# untitled11111.net
KiCad netlist of a schematic drawn in EAGLE
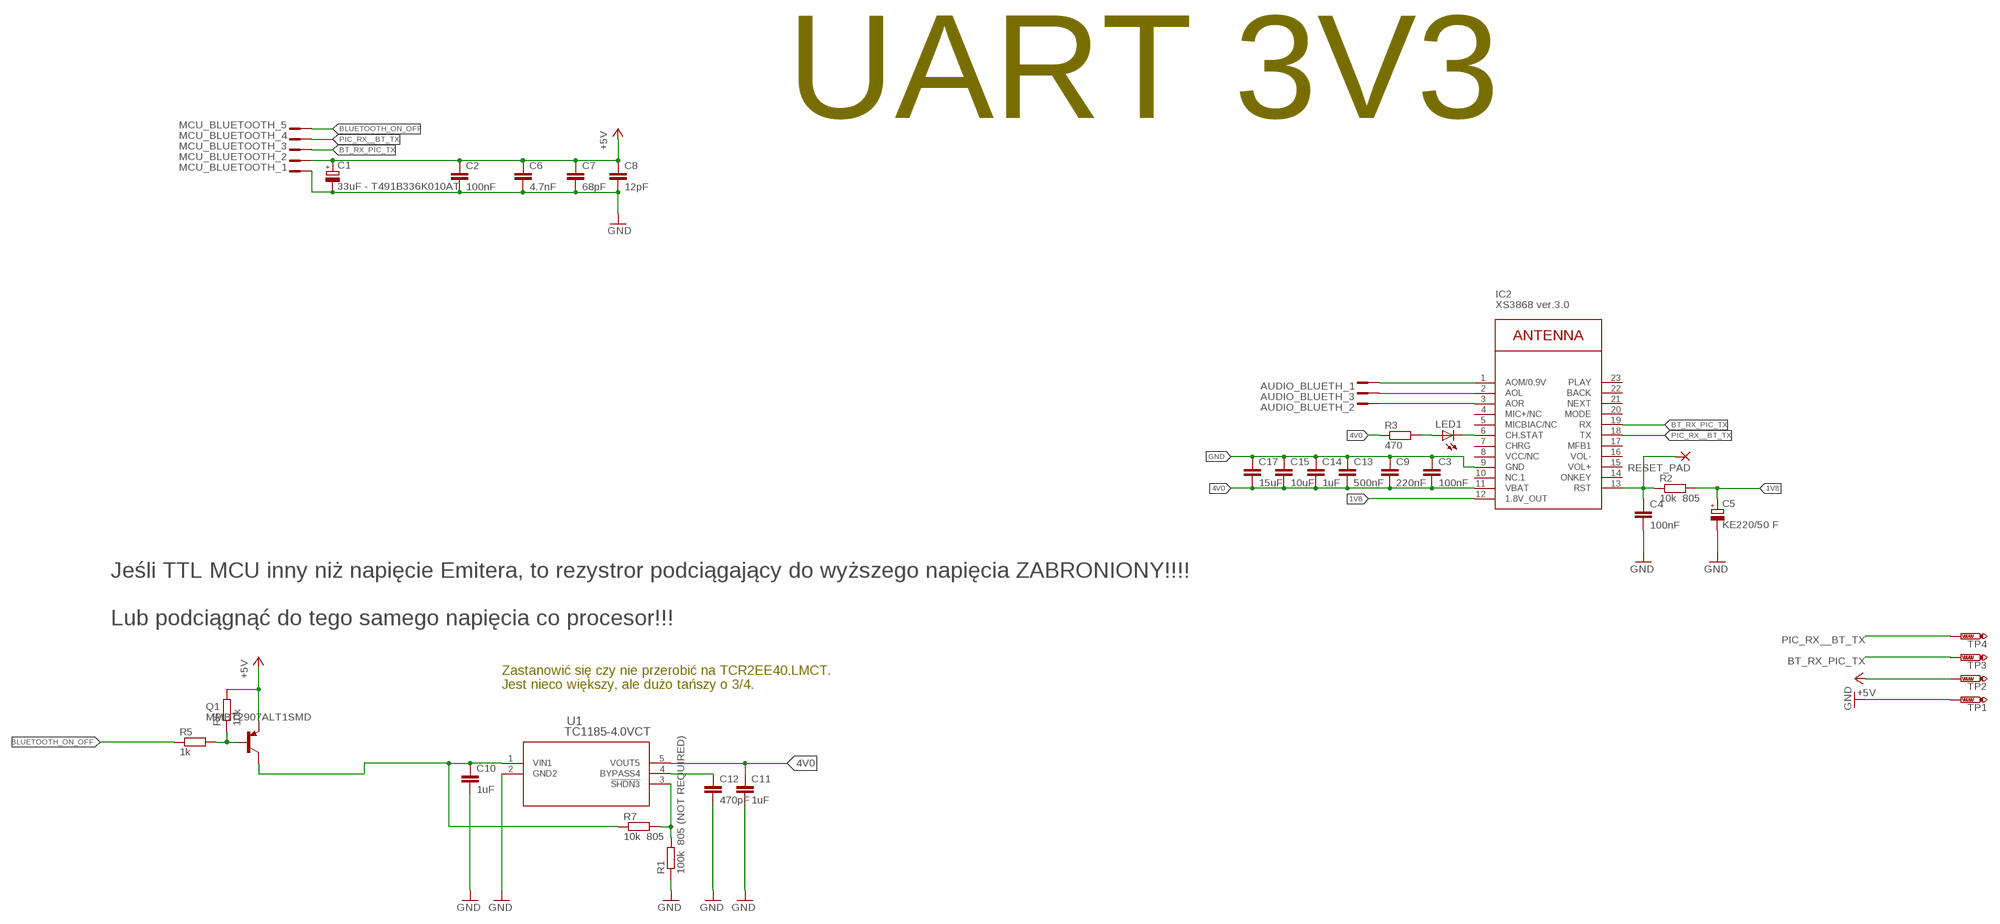
[diagram p0: schematic, sheet 1]

(export (version "E")
  (design (tool "Eeschema 10.0.6"))
  (components
    (comp (ref "AUDIO_BLUETH")
      (value "JST_3_PIN_B3B-PH-KS")
      (footprint "eagle-import:B3B-PH-KS")
      (libsource (lib "eagle-import") (part "JST_3_PIN_B3B-PH-KS"))
    )
    (comp (ref "C1")
      (value "33uF - T491B336K010AT")
      (footprint "eagle-import:SMC_C")
      (libsource (lib "eagle-import") (part "resistor_CPOL-EUSMCC"))
    )
    (comp (ref "C2")
      (value "100nF")
      (footprint "eagle-import:C0805")
      (libsource (lib "eagle-import") (part "C-EUC0805"))
    )
    (comp (ref "C3")
      (value "100nF")
      (footprint "eagle-import:C0805")
      (libsource (lib "eagle-import") (part "C-EUC0805"))
    )
    (comp (ref "C4")
      (value "100nF")
      (footprint "eagle-import:C0805")
      (libsource (lib "eagle-import") (part "C-EUC0805"))
    )
    (comp (ref "C5")
      (value "KE220/50 F")
      (footprint "eagle-import:PANASONIC_G")
      (libsource (lib "eagle-import") (part "CPOL-EUG"))
    )
    (comp (ref "C6")
      (value "4.7nF")
      (footprint "eagle-import:C0805")
      (libsource (lib "eagle-import") (part "C-EUC0805"))
    )
    (comp (ref "C7")
      (value "68pF")
      (footprint "eagle-import:C0805")
      (libsource (lib "eagle-import") (part "C-EUC0805"))
    )
    (comp (ref "C8")
      (value "12pF")
      (footprint "eagle-import:C0805")
      (libsource (lib "eagle-import") (part "C-EUC0805"))
    )
    (comp (ref "C9")
      (value "220nF")
      (footprint "eagle-import:C0805")
      (libsource (lib "eagle-import") (part "C-EUC0805"))
    )
    (comp (ref "C10")
      (value "1uF")
      (footprint "eagle-import:C0805")
      (libsource (lib "eagle-import") (part "C-EUC0805"))
    )
    (comp (ref "C11")
      (value "1uF")
      (footprint "eagle-import:C0805")
      (libsource (lib "eagle-import") (part "C-EUC0805"))
    )
    (comp (ref "C12")
      (value "470pF")
      (footprint "eagle-import:C0805")
      (libsource (lib "eagle-import") (part "C-EUC0805"))
    )
    (comp (ref "C13")
      (value "500nF")
      (footprint "eagle-import:C0805")
      (libsource (lib "eagle-import") (part "C-EUC0805"))
    )
    (comp (ref "C14")
      (value "1uF")
      (footprint "eagle-import:C0805")
      (libsource (lib "eagle-import") (part "C-EUC0805"))
    )
    (comp (ref "C15")
      (value "10uF")
      (footprint "eagle-import:C0805")
      (libsource (lib "eagle-import") (part "C-EUC0805"))
    )
    (comp (ref "C17")
      (value "15uF")
      (footprint "eagle-import:C0805")
      (libsource (lib "eagle-import") (part "C-EUC0805"))
    )
    (comp (ref "IC2")
      (value "XS3868 ver.3.0")
      (footprint "eagle-import:WIRELESS-BLUETOOTH-XS3868")
      (libsource (lib "eagle-import") (part "WIRELESS-BLUETOOTH-XS3868"))
    )
    (comp (ref "LED1")
      (value "LEDSML0805")
      (footprint "eagle-import:SML0805")
      (libsource (lib "eagle-import") (part "LEDSML0805"))
    )
    (comp (ref "MCU_BLUETOOTH")
      (value "JST_5_PIN_B5B-PH-KS")
      (footprint "eagle-import:B5B-PH-KS")
      (libsource (lib "eagle-import") (part "JST_5_PIN_B5B-PH-KS"))
    )
    (comp (ref "Q1")
      (value "MMBT2907ALT1SMD")
      (footprint "eagle-import:SOT23-BEC")
      (libsource (lib "eagle-import") (part "MMBT2907SMDALT1"))
    )
    (comp (ref "R1")
      (value "100k 805 (NOT REQUIRED)")
      (footprint "eagle-import:M0805")
      (libsource (lib "eagle-import") (part "R-EU_M0805"))
    )
    (comp (ref "R2")
      (value "10k 805")
      (footprint "eagle-import:M0805")
      (libsource (lib "eagle-import") (part "R-EU_M0805"))
    )
    (comp (ref "R3")
      (value "470")
      (footprint "eagle-import:M0805")
      (libsource (lib "eagle-import") (part "R-EU_M0805"))
    )
    (comp (ref "R5")
      (value "1k")
      (footprint "eagle-import:M0805")
      (libsource (lib "eagle-import") (part "R-EU_M0805"))
    )
    (comp (ref "R6")
      (value "10k")
      (footprint "eagle-import:M0805")
      (libsource (lib "eagle-import") (part "R-EU_M0805"))
    )
    (comp (ref "R7")
      (value "10k 805")
      (footprint "eagle-import:M0805")
      (libsource (lib "eagle-import") (part "R-EU_M0805"))
    )
    (comp (ref "RESET_PAD")
      (value "SMD2")
      (footprint "eagle-import:SMD1,27-2,54")
      (libsource (lib "eagle-import") (part "SMD2"))
    )
    (comp (ref "TP1")
      (value "PTR1B1,27")
      (footprint "eagle-import:B1,27")
      (libsource (lib "eagle-import") (part "PTR1B1,27"))
    )
    (comp (ref "TP2")
      (value "PTR1B1,27")
      (footprint "eagle-import:B1,27")
      (libsource (lib "eagle-import") (part "PTR1B1,27"))
    )
    (comp (ref "TP3")
      (value "PTR1B1,27")
      (footprint "eagle-import:B1,27")
      (libsource (lib "eagle-import") (part "PTR1B1,27"))
    )
    (comp (ref "TP4")
      (value "PTR1B1,27")
      (footprint "eagle-import:B1,27")
      (libsource (lib "eagle-import") (part "PTR1B1,27"))
    )
    (comp (ref "U1")
      (value "TC1185-4.0VCT")
      (footprint "eagle-import:SOT-23-5_MC-M")
      (fields (field (name "MANUFACTURER_PART_NUMBER") "TC1185X.XXCT713"))
      (libsource (lib "eagle-import") (part "TC1185-X.XXCT713SOT-23-5_MC-M"))
    )
  )
  (nets
    (net (code "1") (name "+5V") (class "Default")
      (node (ref "C1") (pin "+") (pinfunction "+_+") (pintype "passive"))
      (node (ref "C2") (pin "1") (pinfunction "1_1") (pintype "passive"))
      (node (ref "C6") (pin "1") (pinfunction "1_1") (pintype "passive"))
      (node (ref "C7") (pin "1") (pinfunction "1_1") (pintype "passive"))
      (node (ref "C8") (pin "1") (pinfunction "1_1") (pintype "passive"))
      (node (ref "MCU_BLUETOOTH") (pin "P$2") (pinfunction "P$1_P$2") (pintype "bidirectional"))
      (node (ref "Q1") (pin "E") (pinfunction "E_E") (pintype "passive"))
      (node (ref "R6") (pin "2") (pinfunction "2_2") (pintype "passive"))
      (node (ref "TP2") (pin "TP") (pinfunction "TP_TP") (pintype "input"))
    )
    (net (code "2") (name "1V8") (class "Default")
      (node (ref "C5") (pin "+") (pinfunction "+_+") (pintype "passive"))
      (node (ref "IC2") (pin "12") (pinfunction "1.8V_OUT_12") (pintype "power_in"))
      (node (ref "R2") (pin "2") (pinfunction "2_2") (pintype "passive"))
    )
    (net (code "3") (name "4V0") (class "Default")
      (node (ref "C11") (pin "1") (pinfunction "1_1") (pintype "passive"))
      (node (ref "C13") (pin "2") (pinfunction "2_2") (pintype "passive"))
      (node (ref "C14") (pin "2") (pinfunction "2_2") (pintype "passive"))
      (node (ref "C15") (pin "2") (pinfunction "2_2") (pintype "passive"))
      (node (ref "C17") (pin "2") (pinfunction "2_2") (pintype "passive"))
      (node (ref "C3") (pin "2") (pinfunction "2_2") (pintype "passive"))
      (node (ref "C9") (pin "2") (pinfunction "2_2") (pintype "passive"))
      (node (ref "IC2") (pin "11") (pinfunction "VBAT_11") (pintype "power_in"))
      (node (ref "R3") (pin "1") (pinfunction "1_1") (pintype "passive"))
      (node (ref "U1") (pin "5") (pinfunction "VOUT5_5") (pintype "passive"))
    )
    (net (code "4") (name "BLUETOOTH_ON_OFF") (class "Default")
      (node (ref "MCU_BLUETOOTH") (pin "P$5") (pinfunction "P$1_P$5") (pintype "bidirectional"))
      (node (ref "R5") (pin "1") (pinfunction "1_1") (pintype "passive"))
    )
    (net (code "5") (name "BT_RX_PIC_TX") (class "Default")
      (node (ref "IC2") (pin "19") (pinfunction "RX_19") (pintype "bidirectional"))
      (node (ref "MCU_BLUETOOTH") (pin "P$3") (pinfunction "P$1_P$3") (pintype "bidirectional"))
      (node (ref "TP3") (pin "TP") (pinfunction "TP_TP") (pintype "input"))
    )
    (net (code "6") (name "GND") (class "Default")
      (node (ref "C1") (pin "-") (pinfunction "-_-") (pintype "passive"))
      (node (ref "C10") (pin "2") (pinfunction "2_2") (pintype "passive"))
      (node (ref "C11") (pin "2") (pinfunction "2_2") (pintype "passive"))
      (node (ref "C12") (pin "2") (pinfunction "2_2") (pintype "passive"))
      (node (ref "C13") (pin "1") (pinfunction "1_1") (pintype "passive"))
      (node (ref "C14") (pin "1") (pinfunction "1_1") (pintype "passive"))
      (node (ref "C15") (pin "1") (pinfunction "1_1") (pintype "passive"))
      (node (ref "C17") (pin "1") (pinfunction "1_1") (pintype "passive"))
      (node (ref "C2") (pin "2") (pinfunction "2_2") (pintype "passive"))
      (node (ref "C3") (pin "1") (pinfunction "1_1") (pintype "passive"))
      (node (ref "C4") (pin "2") (pinfunction "2_2") (pintype "passive"))
      (node (ref "C5") (pin "-") (pinfunction "-_-") (pintype "passive"))
      (node (ref "C6") (pin "2") (pinfunction "2_2") (pintype "passive"))
      (node (ref "C7") (pin "2") (pinfunction "2_2") (pintype "passive"))
      (node (ref "C8") (pin "2") (pinfunction "2_2") (pintype "passive"))
      (node (ref "C9") (pin "1") (pinfunction "1_1") (pintype "passive"))
      (node (ref "IC2") (pin "9") (pinfunction "GND_9") (pintype "power_in"))
      (node (ref "MCU_BLUETOOTH") (pin "P$1") (pinfunction "P$1_P$1") (pintype "bidirectional"))
      (node (ref "R1") (pin "1") (pinfunction "1_1") (pintype "passive"))
      (node (ref "TP1") (pin "TP") (pinfunction "TP_TP") (pintype "input"))
      (node (ref "U1") (pin "2") (pinfunction "GND2_2") (pintype "passive"))
    )
    (net (code "7") (name "Net-(AUDIO_BLUETHB-P$1)") (class "Default")
      (node (ref "AUDIO_BLUETH") (pin "P$2") (pinfunction "P$1_P$2") (pintype "bidirectional"))
      (node (ref "IC2") (pin "3") (pinfunction "AOR_3") (pintype "output"))
    )
    (net (code "8") (name "Net-(AUDIO_BLUETHC-P$1)") (class "Default")
      (node (ref "AUDIO_BLUETH") (pin "P$3") (pinfunction "P$1_P$3") (pintype "bidirectional"))
      (node (ref "IC2") (pin "2") (pinfunction "AOL_2") (pintype "output"))
    )
    (net (code "9") (name "Net-(IC2-AOM{slash}0.9V)") (class "Default")
      (node (ref "AUDIO_BLUETH") (pin "P$1") (pinfunction "P$1_P$1") (pintype "bidirectional"))
      (node (ref "IC2") (pin "1") (pinfunction "AOM/0.9V_1") (pintype "power_in"))
    )
    (net (code "10") (name "Net-(IC2-CH.STAT)") (class "Default")
      (node (ref "IC2") (pin "6") (pinfunction "CH.STAT_6") (pintype "bidirectional"))
      (node (ref "LED1") (pin "C") (pinfunction "C_C") (pintype "passive"))
    )
    (net (code "11") (name "Net-(IC2-RST)") (class "Default")
      (node (ref "C4") (pin "1") (pinfunction "1_1") (pintype "passive"))
      (node (ref "IC2") (pin "13") (pinfunction "RST_13") (pintype "power_in"))
      (node (ref "R2") (pin "1") (pinfunction "1_1") (pintype "passive"))
      (node (ref "RESET_PAD") (pin "1") (pinfunction "P_1") (pintype "passive"))
    )
    (net (code "12") (name "Net-(LED1-PadA)") (class "Default")
      (node (ref "LED1") (pin "A") (pinfunction "A_A") (pintype "passive"))
      (node (ref "R3") (pin "2") (pinfunction "2_2") (pintype "passive"))
    )
    (net (code "13") (name "Net-(Q1-PadB)") (class "Default")
      (node (ref "Q1") (pin "B") (pinfunction "B_B") (pintype "passive"))
      (node (ref "R5") (pin "2") (pinfunction "2_2") (pintype "passive"))
      (node (ref "R6") (pin "1") (pinfunction "1_1") (pintype "passive"))
    )
    (net (code "14") (name "Net-(U1-BYPASS4)") (class "Default")
      (node (ref "C12") (pin "1") (pinfunction "1_1") (pintype "passive"))
      (node (ref "U1") (pin "4") (pinfunction "BYPASS4_4") (pintype "passive"))
    )
    (net (code "15") (name "Net-(U1-VIN1)") (class "Default")
      (node (ref "C10") (pin "1") (pinfunction "1_1") (pintype "passive"))
      (node (ref "Q1") (pin "C") (pinfunction "C_C") (pintype "passive"))
      (node (ref "R7") (pin "1") (pinfunction "1_1") (pintype "passive"))
      (node (ref "U1") (pin "1") (pinfunction "VIN1_1") (pintype "passive"))
    )
    (net (code "16") (name "Net-(U1-~{SHDN3})") (class "Default")
      (node (ref "R1") (pin "2") (pinfunction "2_2") (pintype "passive"))
      (node (ref "R7") (pin "2") (pinfunction "2_2") (pintype "passive"))
      (node (ref "U1") (pin "3") (pinfunction "~{SHDN3}_3") (pintype "passive"))
    )
    (net (code "17") (name "PIC_RX__BT_TX") (class "Default")
      (node (ref "IC2") (pin "18") (pinfunction "TX_18") (pintype "bidirectional"))
      (node (ref "MCU_BLUETOOTH") (pin "P$4") (pinfunction "P$1_P$4") (pintype "bidirectional"))
      (node (ref "TP4") (pin "TP") (pinfunction "TP_TP") (pintype "input"))
    )
    (net (code "18") (name "unconnected-(IC2-BACK-Pad22)") (class "Default")
      (node (ref "IC2") (pin "22") (pinfunction "BACK_22") (pintype "bidirectional"))
    )
    (net (code "19") (name "unconnected-(IC2-CHRG-Pad7)") (class "Default")
      (node (ref "IC2") (pin "7") (pinfunction "CHRG_7") (pintype "bidirectional"))
    )
    (net (code "20") (name "unconnected-(IC2-MFB1-Pad17)") (class "Default")
      (node (ref "IC2") (pin "17") (pinfunction "MFB1_17") (pintype "passive"))
    )
    (net (code "21") (name "unconnected-(IC2-MIC+{slash}NC-Pad4)") (class "Default")
      (node (ref "IC2") (pin "4") (pinfunction "MIC+/NC_4") (pintype "bidirectional"))
    )
    (net (code "22") (name "unconnected-(IC2-MICBIAC{slash}NC-Pad5)") (class "Default")
      (node (ref "IC2") (pin "5") (pinfunction "MICBIAC/NC_5") (pintype "bidirectional"))
    )
    (net (code "23") (name "unconnected-(IC2-MODE-Pad20)") (class "Default")
      (node (ref "IC2") (pin "20") (pinfunction "MODE_20") (pintype "passive"))
    )
    (net (code "24") (name "unconnected-(IC2-NC.1-Pad10)") (class "Default")
      (node (ref "IC2") (pin "10") (pinfunction "NC.1_10") (pintype "passive"))
    )
    (net (code "25") (name "unconnected-(IC2-NEXT-Pad21)") (class "Default")
      (node (ref "IC2") (pin "21") (pinfunction "NEXT_21") (pintype "bidirectional"))
    )
    (net (code "26") (name "unconnected-(IC2-ONKEY-Pad14)") (class "Default")
      (node (ref "IC2") (pin "14") (pinfunction "ONKEY_14") (pintype "passive"))
    )
    (net (code "27") (name "unconnected-(IC2-PLAY-Pad23)") (class "Default")
      (node (ref "IC2") (pin "23") (pinfunction "PLAY_23") (pintype "bidirectional"))
    )
    (net (code "28") (name "unconnected-(IC2-VCC{slash}NC-Pad8)") (class "Default")
      (node (ref "IC2") (pin "8") (pinfunction "VCC/NC_8") (pintype "bidirectional"))
    )
    (net (code "29") (name "unconnected-(IC2-VOL+-Pad15)") (class "Default")
      (node (ref "IC2") (pin "15") (pinfunction "VOL+_15") (pintype "bidirectional"))
    )
    (net (code "30") (name "unconnected-(IC2-VOL--Pad16)") (class "Default")
      (node (ref "IC2") (pin "16") (pinfunction "VOL-_16") (pintype "bidirectional"))
    )
  )
)
